# HC-SR04-Scanner.net
KiCad netlist of a schematic drawn in EAGLE
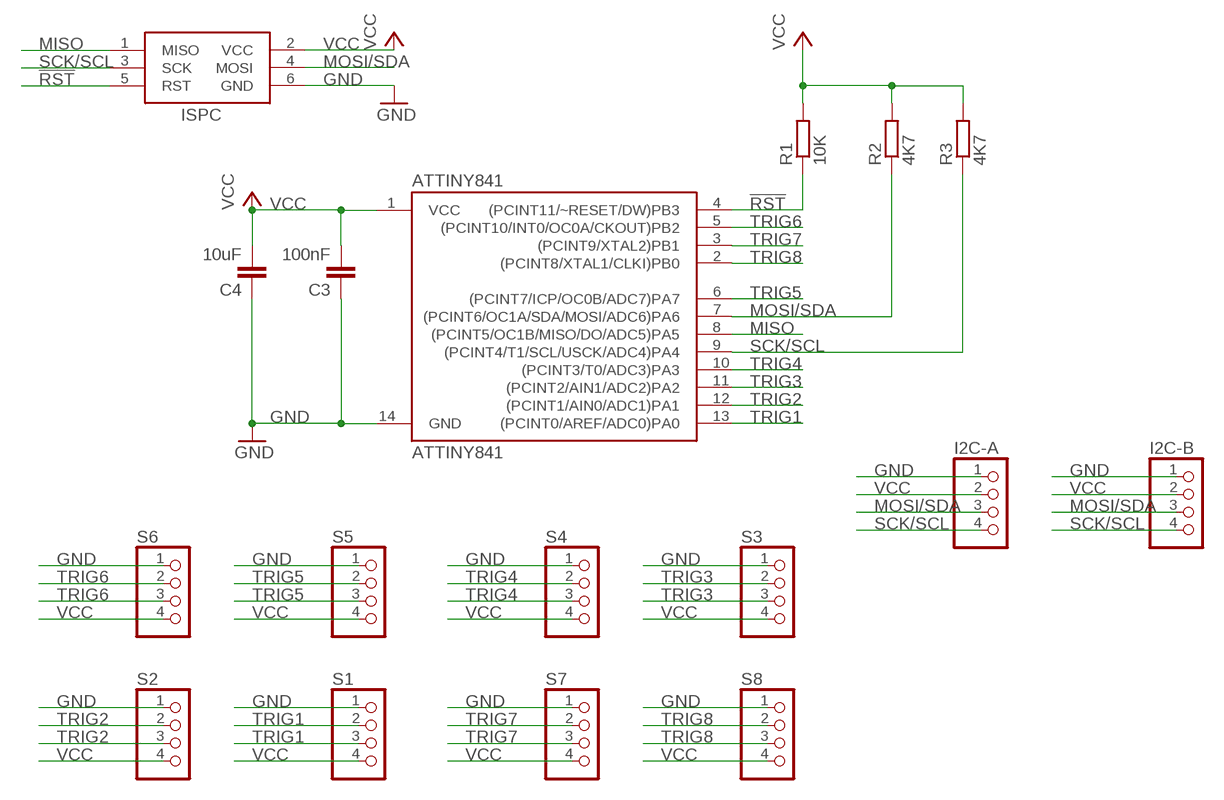
[diagram p0: schematic, sheet 1]

(export (version "E")
  (design (tool "Eeschema 10.0.6"))
  (components
    (comp (ref "ATTINY841")
      (value "ATTINY841")
      (footprint "eagle-import:SO14")
      (libsource (lib "eagle-import") (part "ATTINY84"))
    )
    (comp (ref "C3")
      (value "100nF")
      (footprint "eagle-import:C0805K")
      (libsource (lib "eagle-import") (part "C-EUC0805K"))
    )
    (comp (ref "C4")
      (value "10uF")
      (footprint "eagle-import:C0805K")
      (libsource (lib "eagle-import") (part "C-EUC0805K"))
    )
    (comp (ref "I2C-A")
      (value "PINHD-1X4")
      (footprint "eagle-import:1X04")
      (libsource (lib "eagle-import") (part "PINHD-1X4"))
    )
    (comp (ref "I2C-B")
      (value "PINHD-1X4")
      (footprint "eagle-import:1X04")
      (libsource (lib "eagle-import") (part "PINHD-1X4"))
    )
    (comp (ref "ISPC")
      (value "AVRISP-6")
      (footprint "eagle-import:AVRISP")
      (libsource (lib "eagle-import") (part "AVRISP-6"))
    )
    (comp (ref "R1")
      (value "10K")
      (footprint "eagle-import:R0805")
      (libsource (lib "eagle-import") (part "R-EU_R0805"))
    )
    (comp (ref "R2")
      (value "4K7")
      (footprint "eagle-import:R0805")
      (libsource (lib "eagle-import") (part "R-EU_R0805"))
    )
    (comp (ref "R3")
      (value "4K7")
      (footprint "eagle-import:R0805")
      (libsource (lib "eagle-import") (part "R-EU_R0805"))
    )
    (comp (ref "S1")
      (value "PINHD-1X4")
      (footprint "eagle-import:1X04")
      (libsource (lib "eagle-import") (part "PINHD-1X4"))
    )
    (comp (ref "S2")
      (value "PINHD-1X4")
      (footprint "eagle-import:1X04")
      (libsource (lib "eagle-import") (part "PINHD-1X4"))
    )
    (comp (ref "S3")
      (value "PINHD-1X4")
      (footprint "eagle-import:1X04")
      (libsource (lib "eagle-import") (part "PINHD-1X4"))
    )
    (comp (ref "S4")
      (value "PINHD-1X4")
      (footprint "eagle-import:1X04")
      (libsource (lib "eagle-import") (part "PINHD-1X4"))
    )
    (comp (ref "S5")
      (value "PINHD-1X4")
      (footprint "eagle-import:1X04")
      (libsource (lib "eagle-import") (part "PINHD-1X4"))
    )
    (comp (ref "S6")
      (value "PINHD-1X4")
      (footprint "eagle-import:1X04")
      (libsource (lib "eagle-import") (part "PINHD-1X4"))
    )
    (comp (ref "S7")
      (value "PINHD-1X4")
      (footprint "eagle-import:1X04")
      (libsource (lib "eagle-import") (part "PINHD-1X4"))
    )
    (comp (ref "S8")
      (value "PINHD-1X4")
      (footprint "eagle-import:1X04")
      (libsource (lib "eagle-import") (part "PINHD-1X4"))
    )
  )
  (nets
    (net (code "1") (name "/MISO") (class "Default")
      (node (ref "ATTINY841") (pin "8") (pinfunction "(PCINT5/OC1B/MISO/DO/ADC5)PA5_8") (pintype "bidirectional"))
      (node (ref "ISPC") (pin "1") (pinfunction "MISO_1") (pintype "input"))
    )
    (net (code "2") (name "/MOSI{slash}SDA") (class "Default")
      (node (ref "ATTINY841") (pin "7") (pinfunction "(PCINT6/OC1A/SDA/MOSI/ADC6)PA6_7") (pintype "bidirectional"))
      (node (ref "I2C-A") (pin "3") (pinfunction "3_3") (pintype "passive"))
      (node (ref "I2C-B") (pin "3") (pinfunction "3_3") (pintype "passive"))
      (node (ref "ISPC") (pin "4") (pinfunction "MOSI_4") (pintype "output"))
      (node (ref "R2") (pin "1") (pinfunction "1_1") (pintype "passive"))
    )
    (net (code "3") (name "/SCK{slash}SCL") (class "Default")
      (node (ref "ATTINY841") (pin "9") (pinfunction "(PCINT4/T1/SCL/USCK/ADC4)PA4_9") (pintype "bidirectional"))
      (node (ref "I2C-A") (pin "4") (pinfunction "4_4") (pintype "passive"))
      (node (ref "I2C-B") (pin "4") (pinfunction "4_4") (pintype "passive"))
      (node (ref "ISPC") (pin "3") (pinfunction "SCK_3") (pintype "output"))
      (node (ref "R3") (pin "1") (pinfunction "1_1") (pintype "passive"))
    )
    (net (code "4") (name "/TRIG1") (class "Default")
      (node (ref "ATTINY841") (pin "13") (pinfunction "(PCINT0/AREF/ADC0)PA0_13") (pintype "bidirectional"))
      (node (ref "S1") (pin "2") (pinfunction "2_2") (pintype "passive"))
      (node (ref "S1") (pin "3") (pinfunction "3_3") (pintype "passive"))
    )
    (net (code "5") (name "/TRIG2") (class "Default")
      (node (ref "ATTINY841") (pin "12") (pinfunction "(PCINT1/AIN0/ADC1)PA1_12") (pintype "bidirectional"))
      (node (ref "S2") (pin "2") (pinfunction "2_2") (pintype "passive"))
      (node (ref "S2") (pin "3") (pinfunction "3_3") (pintype "passive"))
    )
    (net (code "6") (name "/TRIG3") (class "Default")
      (node (ref "ATTINY841") (pin "11") (pinfunction "(PCINT2/AIN1/ADC2)PA2_11") (pintype "bidirectional"))
      (node (ref "S3") (pin "2") (pinfunction "2_2") (pintype "passive"))
      (node (ref "S3") (pin "3") (pinfunction "3_3") (pintype "passive"))
    )
    (net (code "7") (name "/TRIG4") (class "Default")
      (node (ref "ATTINY841") (pin "10") (pinfunction "(PCINT3/T0/ADC3)PA3_10") (pintype "bidirectional"))
      (node (ref "S4") (pin "2") (pinfunction "2_2") (pintype "passive"))
      (node (ref "S4") (pin "3") (pinfunction "3_3") (pintype "passive"))
    )
    (net (code "8") (name "/TRIG5") (class "Default")
      (node (ref "ATTINY841") (pin "6") (pinfunction "(PCINT7/ICP/OC0B/ADC7)PA7_6") (pintype "bidirectional"))
      (node (ref "S5") (pin "2") (pinfunction "2_2") (pintype "passive"))
      (node (ref "S5") (pin "3") (pinfunction "3_3") (pintype "passive"))
    )
    (net (code "9") (name "/TRIG6") (class "Default")
      (node (ref "ATTINY841") (pin "5") (pinfunction "(PCINT10/INT0/OC0A/CKOUT)PB2_5") (pintype "bidirectional"))
      (node (ref "S6") (pin "2") (pinfunction "2_2") (pintype "passive"))
      (node (ref "S6") (pin "3") (pinfunction "3_3") (pintype "passive"))
    )
    (net (code "10") (name "/TRIG7") (class "Default")
      (node (ref "ATTINY841") (pin "3") (pinfunction "(PCINT9/XTAL2)PB1_3") (pintype "bidirectional"))
      (node (ref "S7") (pin "2") (pinfunction "2_2") (pintype "passive"))
      (node (ref "S7") (pin "3") (pinfunction "3_3") (pintype "passive"))
    )
    (net (code "11") (name "/TRIG8") (class "Default")
      (node (ref "ATTINY841") (pin "2") (pinfunction "(PCINT8/XTAL1/CLKI)PB0_2") (pintype "bidirectional"))
      (node (ref "S8") (pin "2") (pinfunction "2_2") (pintype "passive"))
      (node (ref "S8") (pin "3") (pinfunction "3_3") (pintype "passive"))
    )
    (net (code "12") (name "/~{RST}") (class "Default")
      (node (ref "ATTINY841") (pin "4") (pinfunction "(PCINT11/~{RESET/DW})PB3_4") (pintype "bidirectional"))
      (node (ref "ISPC") (pin "5") (pinfunction "RST_5") (pintype "output"))
      (node (ref "R1") (pin "1") (pinfunction "1_1") (pintype "passive"))
    )
    (net (code "13") (name "GND") (class "Default")
      (node (ref "ATTINY841") (pin "14") (pinfunction "GND_14") (pintype "bidirectional"))
      (node (ref "C3") (pin "1") (pinfunction "1_1") (pintype "passive"))
      (node (ref "C4") (pin "1") (pinfunction "1_1") (pintype "passive"))
      (node (ref "I2C-A") (pin "1") (pinfunction "1_1") (pintype "passive"))
      (node (ref "I2C-B") (pin "1") (pinfunction "1_1") (pintype "passive"))
      (node (ref "ISPC") (pin "6") (pinfunction "GND_6") (pintype "power_in"))
      (node (ref "S1") (pin "1") (pinfunction "1_1") (pintype "passive"))
      (node (ref "S2") (pin "1") (pinfunction "1_1") (pintype "passive"))
      (node (ref "S3") (pin "1") (pinfunction "1_1") (pintype "passive"))
      (node (ref "S4") (pin "1") (pinfunction "1_1") (pintype "passive"))
      (node (ref "S5") (pin "1") (pinfunction "1_1") (pintype "passive"))
      (node (ref "S6") (pin "1") (pinfunction "1_1") (pintype "passive"))
      (node (ref "S7") (pin "1") (pinfunction "1_1") (pintype "passive"))
      (node (ref "S8") (pin "1") (pinfunction "1_1") (pintype "passive"))
    )
    (net (code "14") (name "VCC") (class "Default")
      (node (ref "ATTINY841") (pin "1") (pinfunction "VCC_1") (pintype "bidirectional"))
      (node (ref "C3") (pin "2") (pinfunction "2_2") (pintype "passive"))
      (node (ref "C4") (pin "2") (pinfunction "2_2") (pintype "passive"))
      (node (ref "I2C-A") (pin "2") (pinfunction "2_2") (pintype "passive"))
      (node (ref "I2C-B") (pin "2") (pinfunction "2_2") (pintype "passive"))
      (node (ref "ISPC") (pin "2") (pinfunction "VCC_2") (pintype "power_in"))
      (node (ref "R1") (pin "2") (pinfunction "2_2") (pintype "passive"))
      (node (ref "R2") (pin "2") (pinfunction "2_2") (pintype "passive"))
      (node (ref "R3") (pin "2") (pinfunction "2_2") (pintype "passive"))
      (node (ref "S1") (pin "4") (pinfunction "4_4") (pintype "passive"))
      (node (ref "S2") (pin "4") (pinfunction "4_4") (pintype "passive"))
      (node (ref "S3") (pin "4") (pinfunction "4_4") (pintype "passive"))
      (node (ref "S4") (pin "4") (pinfunction "4_4") (pintype "passive"))
      (node (ref "S5") (pin "4") (pinfunction "4_4") (pintype "passive"))
      (node (ref "S6") (pin "4") (pinfunction "4_4") (pintype "passive"))
      (node (ref "S7") (pin "4") (pinfunction "4_4") (pintype "passive"))
      (node (ref "S8") (pin "4") (pinfunction "4_4") (pintype "passive"))
    )
  )
)
